# Sheet1.net
KiCad netlist of a schematic drawn in Altium Designer
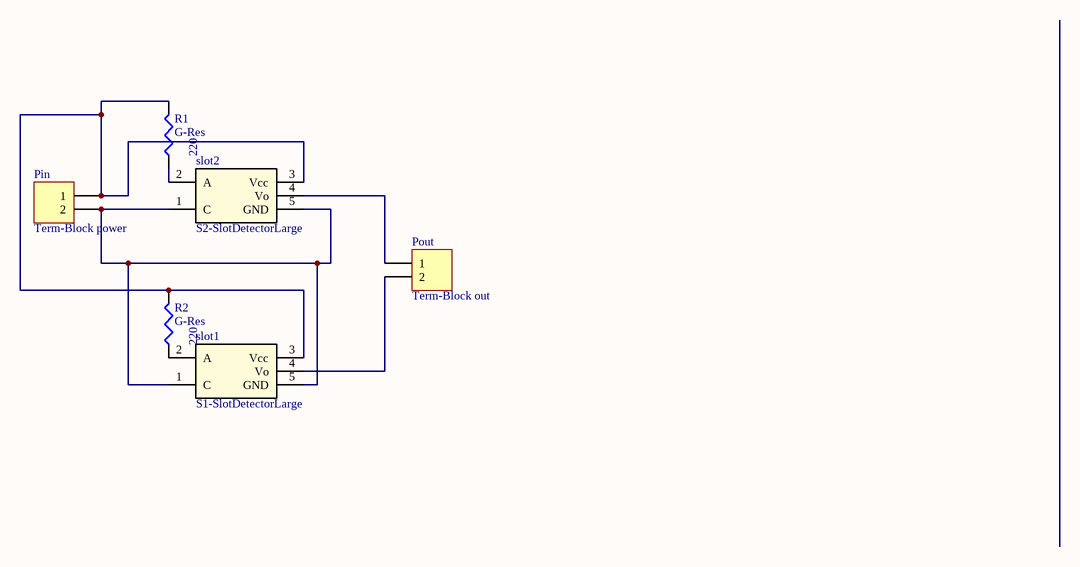
[diagram p0: Sheet1.SchDoc]

(export (version "E")
  (design (tool "Eeschema 10.0.6"))
  (components
    (comp (ref "Pin")
      (value "Term-Block power")
      (footprint "TERM-BLOCK-5.08MM-2POS")
      (description "Terminal-Block 1x2")
      (fields (field (name "PUBLISHER") "Altium Limited"))
      (libsource (lib "PartsDatabaseV16.1") (part "C-Block2"))
    )
    (comp (ref "Pout")
      (value "Term-Block out")
      (footprint "TERM-BLOCK-5.08MM-2POS")
      (description "Terminal-Block 1x2")
      (fields (field (name "PUBLISHER") "Altium Limited"))
      (libsource (lib "") (part "C-Block2_1"))
    )
    (comp (ref "R1")
      (value "G-Res")
      (footprint "Res10mm_LGE1.0")
      (description "Resistor (specify value)")
      (fields (field (name "ALTIUM_VALUE") "220") (field (name "PUBLISHER") "Altium Limited"))
      (libsource (lib "PartsDatabaseV16.1") (part "G-Res"))
    )
    (comp (ref "R2")
      (value "G-Res")
      (footprint "Res10mm_LGE1.0")
      (description "Resistor (specify value)")
      (fields (field (name "ALTIUM_VALUE") "220") (field (name "PUBLISHER") "Altium Limited"))
      (libsource (lib "PartsDatabaseV16.1") (part "G-Res"))
    )
    (comp (ref "slot1")
      (value "S1-SlotDetectorLarge")
      (footprint "S-SLot3")
      (libsource (lib "Additional Parts 391") (part "S2-SlotDetectorLarge"))
    )
    (comp (ref "slot2")
      (value "S2-SlotDetectorLarge")
      (footprint "S-SLot3")
      (libsource (lib "Additional Parts 391") (part "S2-SlotDetectorLarge"))
    )
  )
  (nets
    (net (code "1") (name "Net-(slot1-A)") (class "Default")
      (node (ref "R2") (pin "1") (pinfunction "1_1") (pintype "passive"))
      (node (ref "slot1") (pin "2") (pinfunction "A_2") (pintype "passive"))
    )
    (net (code "2") (name "Net-(slot1-C)") (class "Default")
      (node (ref "Pin") (pin "2") (pinfunction "2_2") (pintype "passive"))
      (node (ref "slot1") (pin "1") (pinfunction "C_1") (pintype "passive"))
      (node (ref "slot1") (pin "5") (pinfunction "GND_5") (pintype "passive"))
      (node (ref "slot2") (pin "1") (pinfunction "C_1") (pintype "passive"))
      (node (ref "slot2") (pin "5") (pinfunction "GND_5") (pintype "passive"))
    )
    (net (code "3") (name "Net-(slot1-Vcc)") (class "Default")
      (node (ref "Pin") (pin "1") (pinfunction "1_1") (pintype "passive"))
      (node (ref "R1") (pin "2") (pinfunction "2_2") (pintype "passive"))
      (node (ref "R2") (pin "2") (pinfunction "2_2") (pintype "passive"))
      (node (ref "slot1") (pin "3") (pinfunction "Vcc_3") (pintype "passive"))
      (node (ref "slot2") (pin "3") (pinfunction "Vcc_3") (pintype "passive"))
    )
    (net (code "4") (name "Net-(slot1-Vo)") (class "Default")
      (node (ref "Pout") (pin "2") (pinfunction "2_2") (pintype "passive"))
      (node (ref "slot1") (pin "4") (pinfunction "Vo_4") (pintype "passive"))
    )
    (net (code "5") (name "Net-(slot2-A)") (class "Default")
      (node (ref "R1") (pin "1") (pinfunction "1_1") (pintype "passive"))
      (node (ref "slot2") (pin "2") (pinfunction "A_2") (pintype "passive"))
    )
    (net (code "6") (name "Net-(slot2-Vo)") (class "Default")
      (node (ref "Pout") (pin "1") (pinfunction "1_1") (pintype "passive"))
      (node (ref "slot2") (pin "4") (pinfunction "Vo_4") (pintype "passive"))
    )
  )
)
